# MCISO-S04-V00-Microcontroller.net
KiCad netlist of a schematic drawn in Altium Designer
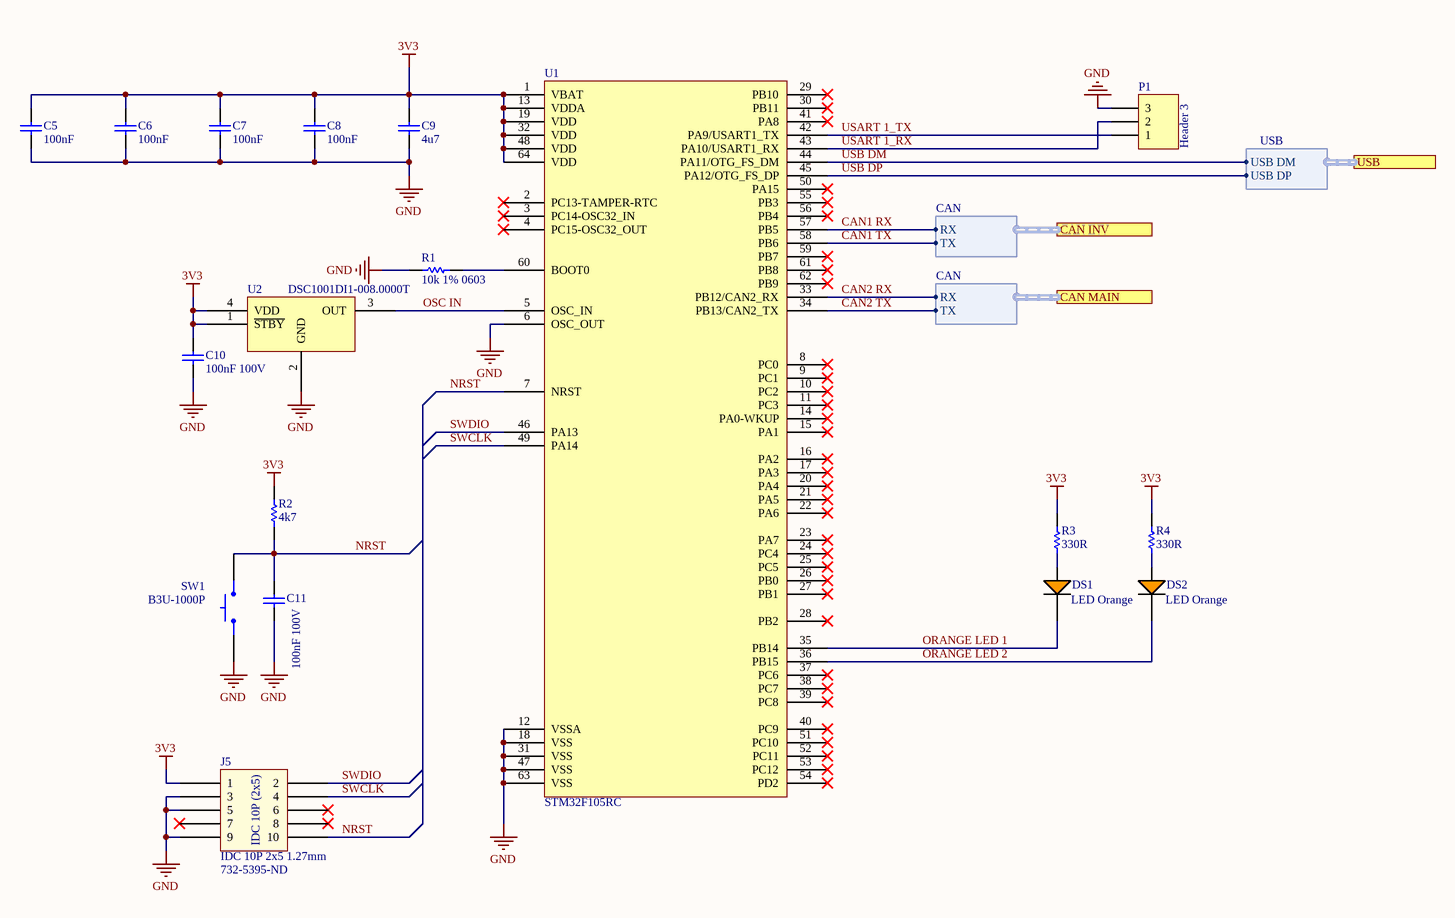
[diagram p0: MCISO-S04-V00-Microcontroller.SchDoc]

(export (version "E")
  (design (tool "Eeschema 10.0.6"))
  (components
    (comp (ref "C5")
      (value "100nF")
      (footprint "Cap_Ceramic_0603")
      (description "Capacitor, Ceramic, SMD, 100nF, 50V, 5%, X7R, 0603")
      (libsource (lib "StandardCapacitors") (part "100nF 50V 5% X7R 0603"))
    )
    (comp (ref "C6")
      (value "100nF")
      (footprint "Cap_Ceramic_0603")
      (description "Capacitor, Ceramic, SMD, 100nF, 50V, 5%, X7R, 0603")
      (libsource (lib "StandardCapacitors") (part "100nF 50V 5% X7R 0603"))
    )
    (comp (ref "C7")
      (value "100nF")
      (footprint "Cap_Ceramic_0603")
      (description "Capacitor, Ceramic, SMD, 100nF, 50V, 5%, X7R, 0603")
      (libsource (lib "StandardCapacitors") (part "100nF 50V 5% X7R 0603"))
    )
    (comp (ref "C8")
      (value "100nF")
      (footprint "Cap_Ceramic_0603")
      (description "Capacitor, Ceramic, SMD, 100nF, 50V, 5%, X7R, 0603")
      (libsource (lib "StandardCapacitors") (part "100nF 50V 5% X7R 0603"))
    )
    (comp (ref "C9")
      (value "4u7")
      (footprint "Cap_Ceramic_0603")
      (description "Capacitor, Ceramic, SMD, 4u7, 50V, 5%, X7R, 0603")
      (libsource (lib "StandardCapacitors") (part "4u7 50V 5% X7R 0603"))
    )
    (comp (ref "C10")
      (value "100nF 100V")
      (footprint "Cap_Ceramic_0603")
      (description "Capacitor, Ceramic, SMD, 100nF, 100V, 5%, X7R, 0603")
      (libsource (lib "StandardCapacitors") (part "100nF 100V 5% X7R 0603"))
    )
    (comp (ref "C11")
      (value "100nF 100V")
      (footprint "Cap_Ceramic_0603")
      (description "Capacitor, Ceramic, SMD, 100nF, 100V, 5%, X7R, 0603")
      (libsource (lib "StandardCapacitors") (part "100nF 100V 5% X7R 0603"))
    )
    (comp (ref "DS1")
      (value "LED Orange")
      (footprint "LED ORANGE 0603")
      (libsource (lib "QUTMS_LEDLibrary") (part "LED ORANGE 0603"))
    )
    (comp (ref "DS2")
      (value "LED Orange")
      (footprint "LED ORANGE 0603")
      (libsource (lib "QUTMS_LEDLibrary") (part "LED ORANGE 0603"))
    )
    (comp (ref "J5")
      (value "IDC 10P 2x5 1.27mm")
      (footprint "IDC 1.27MM 10P")
      (libsource (lib "IDCConnectors") (part "IDC 10P 2x5 1.27mm"))
    )
    (comp (ref "P1")
      (value "Header 3")
      (footprint "HDR1X3")
      (description "Header, 3-Pin")
      (fields (field (name "PUBLISHER") "Altium Limited"))
      (libsource (lib "Miscellaneous Connectors") (part "Header 3"))
    )
    (comp (ref "R1")
      (value "10k 1% 0603")
      (footprint "Res_ThinFilm_0603")
      (description "Resistor, SMD, 20k, 0.1W, 5%, 0603")
      (libsource (lib "QUTMS-MCISOLibrary") (part "20k 1% 0603"))
    )
    (comp (ref "R2")
      (value "4k7")
      (footprint "Res_ThinFilm_0603")
      (description "Resistor, SMD, 4k7, 0.1W, 5%, 0603")
      (libsource (lib "StandardResistors") (part "4k7 5% 0603"))
    )
    (comp (ref "R3")
      (value "330R")
      (footprint "Res_ThinFilm_0603")
      (description "Resistor, SMD, 330R, 0.1W, 5%, 0603")
      (libsource (lib "StandardResistors") (part "330R 5% 0603"))
    )
    (comp (ref "R4")
      (value "330R")
      (footprint "Res_ThinFilm_0603")
      (description "Resistor, SMD, 330R, 0.1W, 5%, 0603")
      (libsource (lib "StandardResistors") (part "330R 5% 0603"))
    )
    (comp (ref "SW1")
      (value "B3U-1000P")
      (footprint "BTN B3U-1000P")
      (description "Omron B3U-1000P Ultra Miniture Switch")
      (libsource (lib "QUTMS_SwitchLibrary") (part "BTN B3U-1000P"))
    )
    (comp (ref "U1")
      (value "STM32F105RC")
      (footprint "STM32F105RC")
      (description "ARM® Cortex®-M3 STM32F1 Microcontroller IC 32-Bit 72MHz 256KB (256K x 8) FLASH 64-LQFP (10x10)")
      (libsource (lib "QUTMS-MCISOLibrary") (part "STM32F105RC"))
    )
    (comp (ref "U2")
      (value "DSC1001DI1-008.0000T")
      (footprint "DSC1001DI1-008.0000TCT-ND")
      (description "on 8MHz XO (Standard) CMOS Oscillator 1.8 ~ 3.3V Standby (Power Down) 4-SMD, No Lead")
      (libsource (lib "QUTMS_CrystalLibrary") (part "DSC1001DI1-008.0000T"))
    )
  )
  (nets
    (net (code "3") (name "/CAN1 RX") (class "Default")
      (node (ref "U1") (pin "57") (pinfunction "PB5_57") (pintype "passive"))
    )
    (net (code "4") (name "/CAN1 TX") (class "Default")
      (node (ref "U1") (pin "58") (pinfunction "PB6_58") (pintype "passive"))
    )
    (net (code "5") (name "/CAN2 RX") (class "Default")
      (node (ref "U1") (pin "33") (pinfunction "PB12/CAN2_RX_33") (pintype "passive"))
    )
    (net (code "6") (name "/CAN2 TX") (class "Default")
      (node (ref "U1") (pin "34") (pinfunction "PB13/CAN2_TX_34") (pintype "passive"))
    )
    (net (code "7") (name "/NRST") (class "Default")
      (node (ref "C11") (pin "2") (pinfunction "2_2") (pintype "passive"))
      (node (ref "J5") (pin "10") (pinfunction "10_10") (pintype "passive"))
      (node (ref "R2") (pin "1") (pinfunction "1_1") (pintype "passive"))
      (node (ref "SW1") (pin "2") (pinfunction "2_2") (pintype "passive"))
      (node (ref "U1") (pin "7") (pinfunction "NRST_7") (pintype "passive"))
    )
    (net (code "8") (name "/ORANGE LED 1") (class "Default")
      (node (ref "DS1") (pin "2") (pinfunction "C_2") (pintype "passive"))
      (node (ref "U1") (pin "35") (pinfunction "PB14_35") (pintype "passive"))
    )
    (net (code "9") (name "/ORANGE LED 2") (class "Default")
      (node (ref "DS2") (pin "2") (pinfunction "C_2") (pintype "passive"))
      (node (ref "U1") (pin "36") (pinfunction "PB15_36") (pintype "passive"))
    )
    (net (code "10") (name "/OSC IN") (class "Default")
      (node (ref "U1") (pin "5") (pinfunction "OSC_IN_5") (pintype "passive"))
      (node (ref "U2") (pin "3") (pinfunction "OUT_3") (pintype "passive"))
    )
    (net (code "11") (name "/SWCLK") (class "Default")
      (node (ref "J5") (pin "4") (pinfunction "4_4") (pintype "passive"))
      (node (ref "U1") (pin "49") (pinfunction "PA14_49") (pintype "passive"))
    )
    (net (code "12") (name "/SWDIO") (class "Default")
      (node (ref "J5") (pin "2") (pinfunction "2_2") (pintype "passive"))
      (node (ref "U1") (pin "46") (pinfunction "PA13_46") (pintype "passive"))
    )
    (net (code "13") (name "/USART 1_RX") (class "Default")
      (node (ref "P1") (pin "2") (pinfunction "2_2") (pintype "passive"))
      (node (ref "U1") (pin "43") (pinfunction "PA10/USART1_RX_43") (pintype "passive"))
    )
    (net (code "14") (name "/USART 1_TX") (class "Default")
      (node (ref "P1") (pin "1") (pinfunction "1_1") (pintype "passive"))
      (node (ref "U1") (pin "42") (pinfunction "PA9/USART1_TX_42") (pintype "passive"))
    )
    (net (code "15") (name "/USB DM") (class "Default")
      (node (ref "U1") (pin "44") (pinfunction "PA11/OTG_FS_DM_44") (pintype "passive"))
    )
    (net (code "16") (name "/USB DP") (class "Default")
      (node (ref "U1") (pin "45") (pinfunction "PA12/OTG_FS_DP_45") (pintype "passive"))
    )
    (net (code "19") (name "3V3") (class "Default")
      (node (ref "C10") (pin "2") (pinfunction "2_2") (pintype "passive"))
      (node (ref "C5") (pin "2") (pinfunction "2_2") (pintype "passive"))
      (node (ref "C6") (pin "2") (pinfunction "2_2") (pintype "passive"))
      (node (ref "C7") (pin "2") (pinfunction "2_2") (pintype "passive"))
      (node (ref "C8") (pin "2") (pinfunction "2_2") (pintype "passive"))
      (node (ref "C9") (pin "2") (pinfunction "2_2") (pintype "passive"))
      (node (ref "J5") (pin "1") (pinfunction "1_1") (pintype "passive"))
      (node (ref "R2") (pin "2") (pinfunction "2_2") (pintype "passive"))
      (node (ref "R3") (pin "2") (pinfunction "2_2") (pintype "passive"))
      (node (ref "R4") (pin "2") (pinfunction "2_2") (pintype "passive"))
      (node (ref "U1") (pin "1") (pinfunction "VBAT_1") (pintype "passive"))
      (node (ref "U1") (pin "13") (pinfunction "VDDA_13") (pintype "passive"))
      (node (ref "U1") (pin "19") (pinfunction "VDD_19") (pintype "passive"))
      (node (ref "U1") (pin "32") (pinfunction "VDD_32") (pintype "passive"))
      (node (ref "U1") (pin "48") (pinfunction "VDD_48") (pintype "passive"))
      (node (ref "U1") (pin "64") (pinfunction "VDD_64") (pintype "passive"))
      (node (ref "U2") (pin "1") (pinfunction "~{STBY}_1") (pintype "passive"))
      (node (ref "U2") (pin "4") (pinfunction "VDD_4") (pintype "passive"))
    )
    (net (code "20") (name "GND") (class "Default")
      (node (ref "C10") (pin "1") (pinfunction "1_1") (pintype "passive"))
      (node (ref "C11") (pin "1") (pinfunction "1_1") (pintype "passive"))
      (node (ref "C5") (pin "1") (pinfunction "1_1") (pintype "passive"))
      (node (ref "C6") (pin "1") (pinfunction "1_1") (pintype "passive"))
      (node (ref "C7") (pin "1") (pinfunction "1_1") (pintype "passive"))
      (node (ref "C8") (pin "1") (pinfunction "1_1") (pintype "passive"))
      (node (ref "C9") (pin "1") (pinfunction "1_1") (pintype "passive"))
      (node (ref "J5") (pin "3") (pinfunction "3_3") (pintype "passive"))
      (node (ref "J5") (pin "5") (pinfunction "5_5") (pintype "passive"))
      (node (ref "J5") (pin "9") (pinfunction "9_9") (pintype "passive"))
      (node (ref "P1") (pin "3") (pinfunction "3_3") (pintype "passive"))
      (node (ref "R1") (pin "1") (pinfunction "1_1") (pintype "passive"))
      (node (ref "SW1") (pin "1") (pinfunction "1_1") (pintype "passive"))
      (node (ref "U1") (pin "12") (pinfunction "VSSA_12") (pintype "passive"))
      (node (ref "U1") (pin "18") (pinfunction "VSS_18") (pintype "passive"))
      (node (ref "U1") (pin "31") (pinfunction "VSS_31") (pintype "passive"))
      (node (ref "U1") (pin "47") (pinfunction "VSS_47") (pintype "passive"))
      (node (ref "U1") (pin "6") (pinfunction "OSC_OUT_6") (pintype "passive"))
      (node (ref "U1") (pin "63") (pinfunction "VSS_63") (pintype "passive"))
      (node (ref "U2") (pin "2") (pinfunction "GND_2") (pintype "passive"))
    )
    (net (code "21") (name "Net-(DS1-A)") (class "Default")
      (node (ref "DS1") (pin "1") (pinfunction "A_1") (pintype "passive"))
      (node (ref "R3") (pin "1") (pinfunction "1_1") (pintype "passive"))
    )
    (net (code "22") (name "Net-(DS2-A)") (class "Default")
      (node (ref "DS2") (pin "1") (pinfunction "A_1") (pintype "passive"))
      (node (ref "R4") (pin "1") (pinfunction "1_1") (pintype "passive"))
    )
    (net (code "23") (name "Net-(U1-BOOT0)") (class "Default")
      (node (ref "R1") (pin "2") (pinfunction "2_2") (pintype "passive"))
      (node (ref "U1") (pin "60") (pinfunction "BOOT0_60") (pintype "passive"))
    )
    (net (code "24") (name "unconnected-(J5-Pad6)") (class "Default")
      (node (ref "J5") (pin "6") (pinfunction "6_6") (pintype "passive+no_connect"))
    )
    (net (code "25") (name "unconnected-(J5-Pad7)") (class "Default")
      (node (ref "J5") (pin "7") (pinfunction "7_7") (pintype "passive+no_connect"))
    )
    (net (code "26") (name "unconnected-(J5-Pad8)") (class "Default")
      (node (ref "J5") (pin "8") (pinfunction "8_8") (pintype "passive+no_connect"))
    )
    (net (code "27") (name "unconnected-(U1-PA0-WKUP-Pad14)") (class "Default")
      (node (ref "U1") (pin "14") (pinfunction "PA0-WKUP_14") (pintype "passive+no_connect"))
    )
    (net (code "28") (name "unconnected-(U1-PA1-Pad15)") (class "Default")
      (node (ref "U1") (pin "15") (pinfunction "PA1_15") (pintype "passive+no_connect"))
    )
    (net (code "29") (name "unconnected-(U1-PA2-Pad16)") (class "Default")
      (node (ref "U1") (pin "16") (pinfunction "PA2_16") (pintype "passive+no_connect"))
    )
    (net (code "30") (name "unconnected-(U1-PA3-Pad17)") (class "Default")
      (node (ref "U1") (pin "17") (pinfunction "PA3_17") (pintype "passive+no_connect"))
    )
    (net (code "31") (name "unconnected-(U1-PA4-Pad20)") (class "Default")
      (node (ref "U1") (pin "20") (pinfunction "PA4_20") (pintype "passive+no_connect"))
    )
    (net (code "32") (name "unconnected-(U1-PA5-Pad21)") (class "Default")
      (node (ref "U1") (pin "21") (pinfunction "PA5_21") (pintype "passive+no_connect"))
    )
    (net (code "33") (name "unconnected-(U1-PA6-Pad22)") (class "Default")
      (node (ref "U1") (pin "22") (pinfunction "PA6_22") (pintype "passive+no_connect"))
    )
    (net (code "34") (name "unconnected-(U1-PA7-Pad23)") (class "Default")
      (node (ref "U1") (pin "23") (pinfunction "PA7_23") (pintype "passive+no_connect"))
    )
    (net (code "35") (name "unconnected-(U1-PA8-Pad41)") (class "Default")
      (node (ref "U1") (pin "41") (pinfunction "PA8_41") (pintype "passive+no_connect"))
    )
    (net (code "36") (name "unconnected-(U1-PA15-Pad50)") (class "Default")
      (node (ref "U1") (pin "50") (pinfunction "PA15_50") (pintype "passive+no_connect"))
    )
    (net (code "37") (name "unconnected-(U1-PB0-Pad26)") (class "Default")
      (node (ref "U1") (pin "26") (pinfunction "PB0_26") (pintype "passive+no_connect"))
    )
    (net (code "38") (name "unconnected-(U1-PB1-Pad27)") (class "Default")
      (node (ref "U1") (pin "27") (pinfunction "PB1_27") (pintype "passive+no_connect"))
    )
    (net (code "39") (name "unconnected-(U1-PB2-Pad28)") (class "Default")
      (node (ref "U1") (pin "28") (pinfunction "PB2_28") (pintype "passive+no_connect"))
    )
    (net (code "40") (name "unconnected-(U1-PB3-Pad55)") (class "Default")
      (node (ref "U1") (pin "55") (pinfunction "PB3_55") (pintype "passive+no_connect"))
    )
    (net (code "41") (name "unconnected-(U1-PB4-Pad56)") (class "Default")
      (node (ref "U1") (pin "56") (pinfunction "PB4_56") (pintype "passive+no_connect"))
    )
    (net (code "42") (name "unconnected-(U1-PB7-Pad59)") (class "Default")
      (node (ref "U1") (pin "59") (pinfunction "PB7_59") (pintype "passive+no_connect"))
    )
    (net (code "43") (name "unconnected-(U1-PB8-Pad61)") (class "Default")
      (node (ref "U1") (pin "61") (pinfunction "PB8_61") (pintype "passive+no_connect"))
    )
    (net (code "44") (name "unconnected-(U1-PB9-Pad62)") (class "Default")
      (node (ref "U1") (pin "62") (pinfunction "PB9_62") (pintype "passive+no_connect"))
    )
    (net (code "45") (name "unconnected-(U1-PB10-Pad29)") (class "Default")
      (node (ref "U1") (pin "29") (pinfunction "PB10_29") (pintype "passive+no_connect"))
    )
    (net (code "46") (name "unconnected-(U1-PB11-Pad30)") (class "Default")
      (node (ref "U1") (pin "30") (pinfunction "PB11_30") (pintype "passive+no_connect"))
    )
    (net (code "47") (name "unconnected-(U1-PC0-Pad8)") (class "Default")
      (node (ref "U1") (pin "8") (pinfunction "PC0_8") (pintype "passive+no_connect"))
    )
    (net (code "48") (name "unconnected-(U1-PC1-Pad9)") (class "Default")
      (node (ref "U1") (pin "9") (pinfunction "PC1_9") (pintype "passive+no_connect"))
    )
    (net (code "49") (name "unconnected-(U1-PC2-Pad10)") (class "Default")
      (node (ref "U1") (pin "10") (pinfunction "PC2_10") (pintype "passive+no_connect"))
    )
    (net (code "50") (name "unconnected-(U1-PC3-Pad11)") (class "Default")
      (node (ref "U1") (pin "11") (pinfunction "PC3_11") (pintype "passive+no_connect"))
    )
    (net (code "51") (name "unconnected-(U1-PC4-Pad24)") (class "Default")
      (node (ref "U1") (pin "24") (pinfunction "PC4_24") (pintype "passive+no_connect"))
    )
    (net (code "52") (name "unconnected-(U1-PC5-Pad25)") (class "Default")
      (node (ref "U1") (pin "25") (pinfunction "PC5_25") (pintype "passive+no_connect"))
    )
    (net (code "53") (name "unconnected-(U1-PC6-Pad37)") (class "Default")
      (node (ref "U1") (pin "37") (pinfunction "PC6_37") (pintype "passive+no_connect"))
    )
    (net (code "54") (name "unconnected-(U1-PC7-Pad38)") (class "Default")
      (node (ref "U1") (pin "38") (pinfunction "PC7_38") (pintype "passive+no_connect"))
    )
    (net (code "55") (name "unconnected-(U1-PC8-Pad39)") (class "Default")
      (node (ref "U1") (pin "39") (pinfunction "PC8_39") (pintype "passive+no_connect"))
    )
    (net (code "56") (name "unconnected-(U1-PC9-Pad40)") (class "Default")
      (node (ref "U1") (pin "40") (pinfunction "PC9_40") (pintype "passive+no_connect"))
    )
    (net (code "57") (name "unconnected-(U1-PC10-Pad51)") (class "Default")
      (node (ref "U1") (pin "51") (pinfunction "PC10_51") (pintype "passive+no_connect"))
    )
    (net (code "58") (name "unconnected-(U1-PC11-Pad52)") (class "Default")
      (node (ref "U1") (pin "52") (pinfunction "PC11_52") (pintype "passive+no_connect"))
    )
    (net (code "59") (name "unconnected-(U1-PC12-Pad53)") (class "Default")
      (node (ref "U1") (pin "53") (pinfunction "PC12_53") (pintype "passive+no_connect"))
    )
    (net (code "60") (name "unconnected-(U1-PC13-TAMPER-RTC-Pad2)") (class "Default")
      (node (ref "U1") (pin "2") (pinfunction "PC13-TAMPER-RTC_2") (pintype "passive+no_connect"))
    )
    (net (code "61") (name "unconnected-(U1-PC14-OSC32_IN-Pad3)") (class "Default")
      (node (ref "U1") (pin "3") (pinfunction "PC14-OSC32_IN_3") (pintype "passive+no_connect"))
    )
    (net (code "62") (name "unconnected-(U1-PC15-OSC32_OUT-Pad4)") (class "Default")
      (node (ref "U1") (pin "4") (pinfunction "PC15-OSC32_OUT_4") (pintype "passive+no_connect"))
    )
    (net (code "63") (name "unconnected-(U1-PD2-Pad54)") (class "Default")
      (node (ref "U1") (pin "54") (pinfunction "PD2_54") (pintype "passive+no_connect"))
    )
  )
)
